# bump-sensor.net
KiCad netlist of a schematic drawn in EAGLE
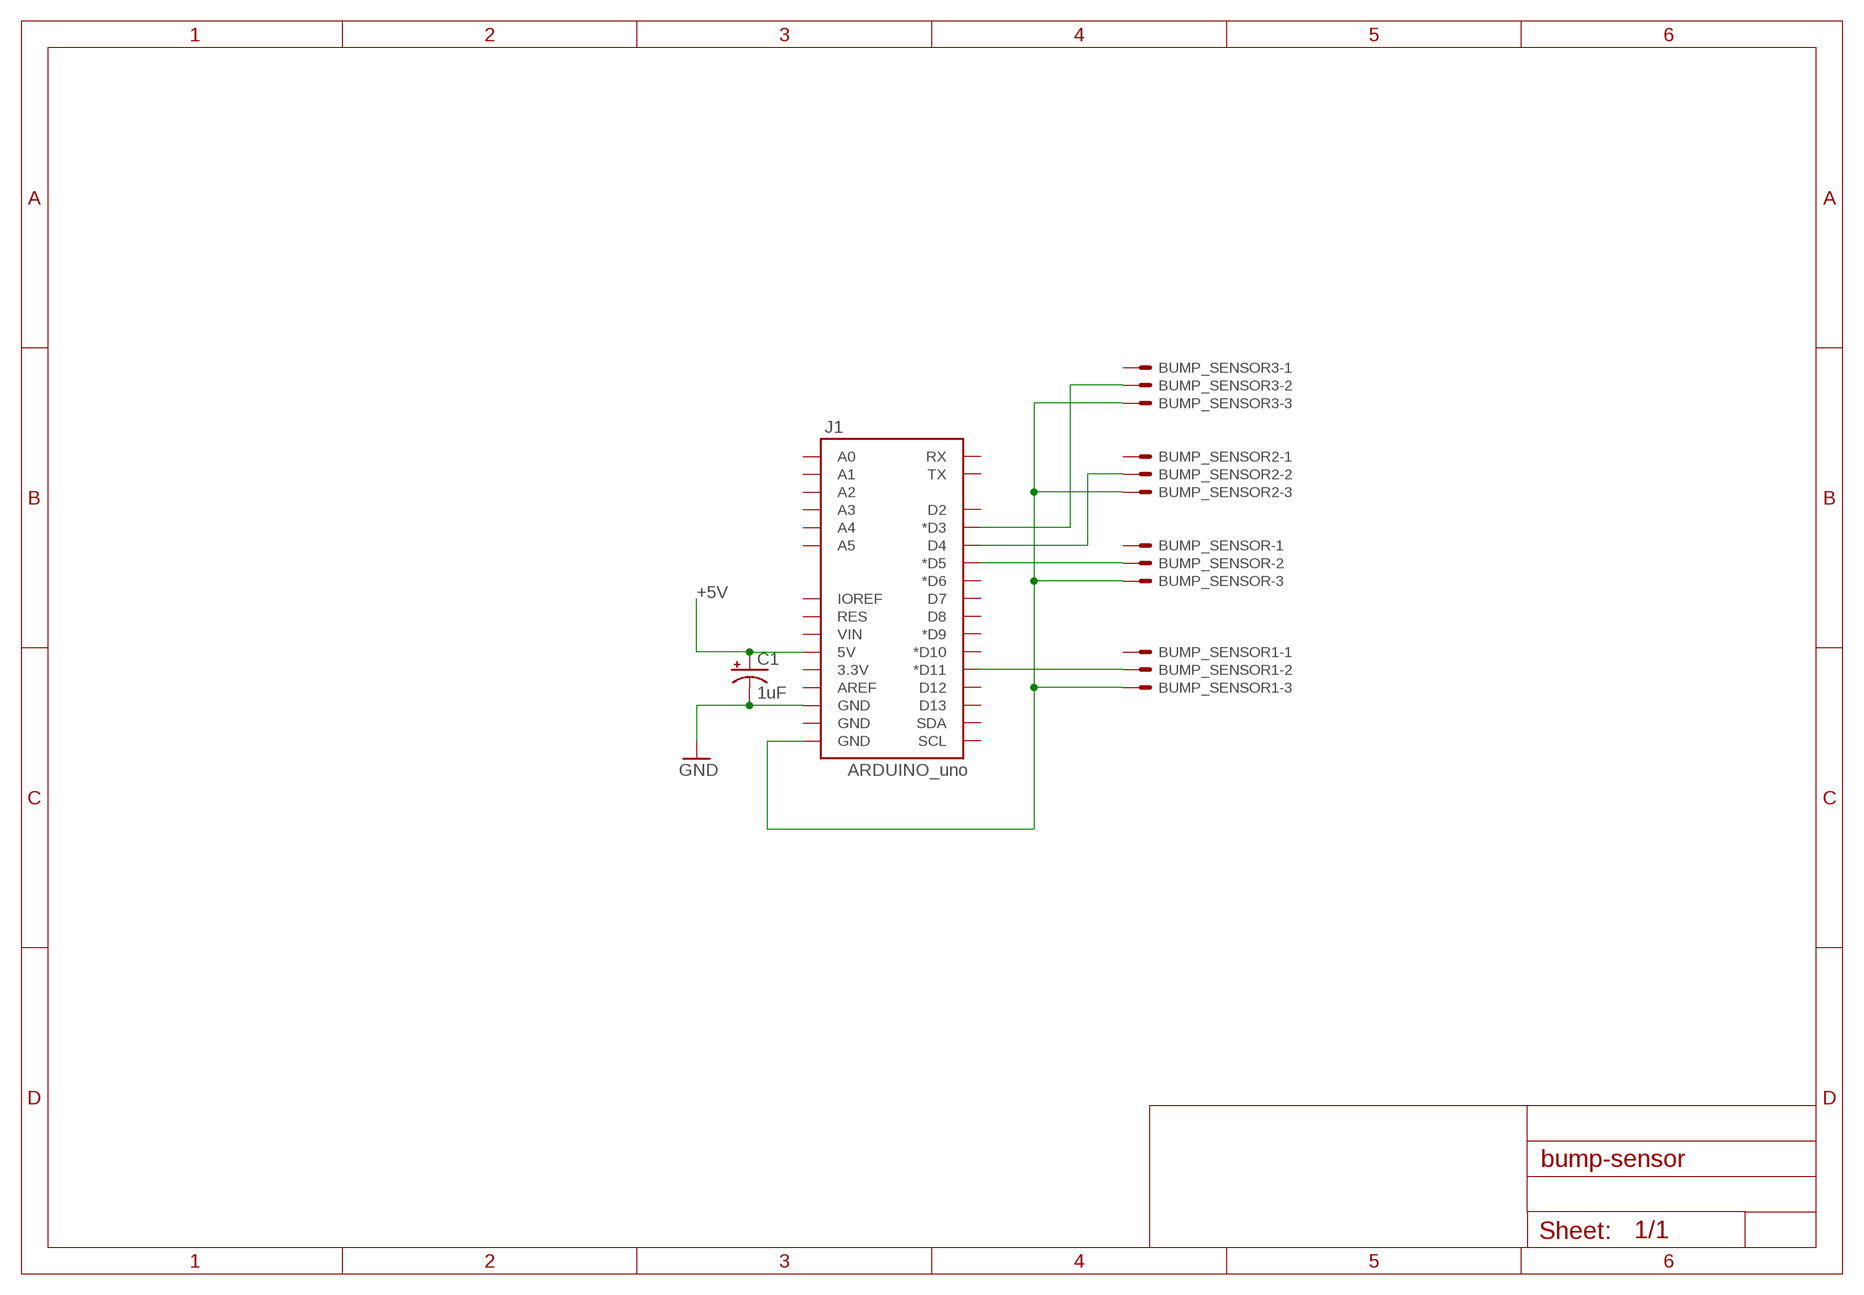
[diagram p0: schematic, sheet 1]

(export (version "E")
  (design (tool "Eeschema 10.0.6"))
  (components
    (comp (ref "BUMP_SENSOR")
      (value "22-23-2031")
      (footprint "eagle-import:22-23-2031")
      (fields (field (name "MF") "MOLEX"))
      (libsource (lib "eagle-import") (part "22-23-2031"))
    )
    (comp (ref "BUMP_SENSOR1")
      (value "22-23-2031")
      (footprint "eagle-import:22-23-2031")
      (fields (field (name "MF") "MOLEX"))
      (libsource (lib "eagle-import") (part "22-23-2031"))
    )
    (comp (ref "BUMP_SENSOR2")
      (value "22-23-2031")
      (footprint "eagle-import:22-23-2031")
      (fields (field (name "MF") "MOLEX"))
      (libsource (lib "eagle-import") (part "22-23-2031"))
    )
    (comp (ref "BUMP_SENSOR3")
      (value "22-23-2031")
      (footprint "eagle-import:22-23-2031")
      (fields (field (name "MF") "MOLEX"))
      (libsource (lib "eagle-import") (part "22-23-2031"))
    )
    (comp (ref "C1")
      (value "1uF")
      (footprint "eagle-import:EIA3216")
      (libsource (lib "eagle-import") (part "CAP_POL1206"))
    )
    (comp (ref "J1")
      (value "ARDUINO_uno")
      (footprint "eagle-import:UNO_R3_SHIELD")
      (libsource (lib "eagle-import") (part "ARDUINO_R3_SHIELD"))
    )
  )
  (nets
    (net (code "1") (name "/+5V") (class "Default")
      (node (ref "C1") (pin "A") (pinfunction "+_A") (pintype "passive"))
      (node (ref "J1") (pin "5V") (pinfunction "5V_5V") (pintype "bidirectional"))
    )
    (net (code "2") (name "GND") (class "Default")
      (node (ref "C1") (pin "C") (pinfunction "-_C") (pintype "passive"))
      (node (ref "J1") (pin "GND@2") (pinfunction "GND_GND@2") (pintype "bidirectional"))
    )
    (net (code "3") (name "Net-(BUMP_SENSOR1B-S)") (class "Default")
      (node (ref "BUMP_SENSOR1") (pin "2") (pinfunction "S_2") (pintype "passive"))
      (node (ref "J1") (pin "D11") (pinfunction "*D11_D11") (pintype "bidirectional"))
    )
    (net (code "4") (name "Net-(BUMP_SENSOR1C-S)") (class "Default")
      (node (ref "BUMP_SENSOR") (pin "3") (pinfunction "S_3") (pintype "passive"))
      (node (ref "BUMP_SENSOR1") (pin "3") (pinfunction "S_3") (pintype "passive"))
      (node (ref "BUMP_SENSOR2") (pin "3") (pinfunction "S_3") (pintype "passive"))
      (node (ref "BUMP_SENSOR3") (pin "3") (pinfunction "S_3") (pintype "passive"))
      (node (ref "J1") (pin "GND@0") (pinfunction "GND_GND@0") (pintype "bidirectional"))
    )
    (net (code "5") (name "Net-(BUMP_SENSOR2B-S)") (class "Default")
      (node (ref "BUMP_SENSOR2") (pin "2") (pinfunction "S_2") (pintype "passive"))
      (node (ref "J1") (pin "D4") (pinfunction "D4_D4") (pintype "bidirectional"))
    )
    (net (code "6") (name "Net-(BUMP_SENSOR3B-S)") (class "Default")
      (node (ref "BUMP_SENSOR3") (pin "2") (pinfunction "S_2") (pintype "passive"))
      (node (ref "J1") (pin "D3") (pinfunction "*D3_D3") (pintype "bidirectional"))
    )
    (net (code "7") (name "Net-(BUMP_SENSORB-S)") (class "Default")
      (node (ref "BUMP_SENSOR") (pin "2") (pinfunction "S_2") (pintype "passive"))
      (node (ref "J1") (pin "D5") (pinfunction "*D5_D5") (pintype "bidirectional"))
    )
    (net (code "8") (name "unconnected-(BUMP_SENSOR1A-S-Pad1)") (class "Default")
      (node (ref "BUMP_SENSOR1") (pin "1") (pinfunction "S_1") (pintype "passive"))
    )
    (net (code "9") (name "unconnected-(BUMP_SENSOR2A-S-Pad1)") (class "Default")
      (node (ref "BUMP_SENSOR2") (pin "1") (pinfunction "S_1") (pintype "passive"))
    )
    (net (code "10") (name "unconnected-(BUMP_SENSOR3A-S-Pad1)") (class "Default")
      (node (ref "BUMP_SENSOR3") (pin "1") (pinfunction "S_1") (pintype "passive"))
    )
    (net (code "11") (name "unconnected-(BUMP_SENSORA-S-Pad1)") (class "Default")
      (node (ref "BUMP_SENSOR") (pin "1") (pinfunction "S_1") (pintype "passive"))
    )
    (net (code "12") (name "unconnected-(J1-*D6-PadD6)") (class "Default")
      (node (ref "J1") (pin "D6") (pinfunction "*D6_D6") (pintype "bidirectional"))
    )
    (net (code "13") (name "unconnected-(J1-*D9-PadD9)") (class "Default")
      (node (ref "J1") (pin "D9") (pinfunction "*D9_D9") (pintype "bidirectional"))
    )
    (net (code "14") (name "unconnected-(J1-*D10-PadD10)") (class "Default")
      (node (ref "J1") (pin "D10") (pinfunction "*D10_D10") (pintype "bidirectional"))
    )
    (net (code "15") (name "unconnected-(J1-GND-PadGND@1)") (class "Default")
      (node (ref "J1") (pin "GND@1") (pinfunction "GND_GND@1") (pintype "bidirectional"))
    )
    (net (code "16") (name "unconnected-(J1-Pad3.3V)") (class "Default")
      (node (ref "J1") (pin "3.3V") (pinfunction "3.3V_3.3V") (pintype "bidirectional"))
    )
    (net (code "17") (name "unconnected-(J1-PadA0)") (class "Default")
      (node (ref "J1") (pin "A0") (pinfunction "A0_A0") (pintype "bidirectional"))
    )
    (net (code "18") (name "unconnected-(J1-PadA1)") (class "Default")
      (node (ref "J1") (pin "A1") (pinfunction "A1_A1") (pintype "bidirectional"))
    )
    (net (code "19") (name "unconnected-(J1-PadA2)") (class "Default")
      (node (ref "J1") (pin "A2") (pinfunction "A2_A2") (pintype "bidirectional"))
    )
    (net (code "20") (name "unconnected-(J1-PadA3)") (class "Default")
      (node (ref "J1") (pin "A3") (pinfunction "A3_A3") (pintype "bidirectional"))
    )
    (net (code "21") (name "unconnected-(J1-PadA4)") (class "Default")
      (node (ref "J1") (pin "A4") (pinfunction "A4_A4") (pintype "bidirectional"))
    )
    (net (code "22") (name "unconnected-(J1-PadA5)") (class "Default")
      (node (ref "J1") (pin "A5") (pinfunction "A5_A5") (pintype "bidirectional"))
    )
    (net (code "23") (name "unconnected-(J1-PadAREF)") (class "Default")
      (node (ref "J1") (pin "AREF") (pinfunction "AREF_AREF") (pintype "bidirectional"))
    )
    (net (code "24") (name "unconnected-(J1-PadD2)") (class "Default")
      (node (ref "J1") (pin "D2") (pinfunction "D2_D2") (pintype "bidirectional"))
    )
    (net (code "25") (name "unconnected-(J1-PadD7)") (class "Default")
      (node (ref "J1") (pin "D7") (pinfunction "D7_D7") (pintype "bidirectional"))
    )
    (net (code "26") (name "unconnected-(J1-PadD8)") (class "Default")
      (node (ref "J1") (pin "D8") (pinfunction "D8_D8") (pintype "bidirectional"))
    )
    (net (code "27") (name "unconnected-(J1-PadD12)") (class "Default")
      (node (ref "J1") (pin "D12") (pinfunction "D12_D12") (pintype "bidirectional"))
    )
    (net (code "28") (name "unconnected-(J1-PadD13)") (class "Default")
      (node (ref "J1") (pin "D13") (pinfunction "D13_D13") (pintype "bidirectional"))
    )
    (net (code "29") (name "unconnected-(J1-PadIOREF)") (class "Default")
      (node (ref "J1") (pin "IOREF") (pinfunction "IOREF_IOREF") (pintype "bidirectional"))
    )
    (net (code "30") (name "unconnected-(J1-PadRES)") (class "Default")
      (node (ref "J1") (pin "RES") (pinfunction "RES_RES") (pintype "bidirectional"))
    )
    (net (code "31") (name "unconnected-(J1-PadRX)") (class "Default")
      (node (ref "J1") (pin "RX") (pinfunction "RX_RX") (pintype "bidirectional"))
    )
    (net (code "32") (name "unconnected-(J1-PadSCL)") (class "Default")
      (node (ref "J1") (pin "SCL") (pinfunction "SCL_SCL") (pintype "bidirectional"))
    )
    (net (code "33") (name "unconnected-(J1-PadSDA)") (class "Default")
      (node (ref "J1") (pin "SDA") (pinfunction "SDA_SDA") (pintype "bidirectional"))
    )
    (net (code "34") (name "unconnected-(J1-PadTX)") (class "Default")
      (node (ref "J1") (pin "TX") (pinfunction "TX_TX") (pintype "bidirectional"))
    )
    (net (code "35") (name "unconnected-(J1-PadVIN)") (class "Default")
      (node (ref "J1") (pin "VIN") (pinfunction "VIN_VIN") (pintype "bidirectional"))
    )
  )
)
